# game_board.net
KiCad netlist of a schematic drawn in EAGLE
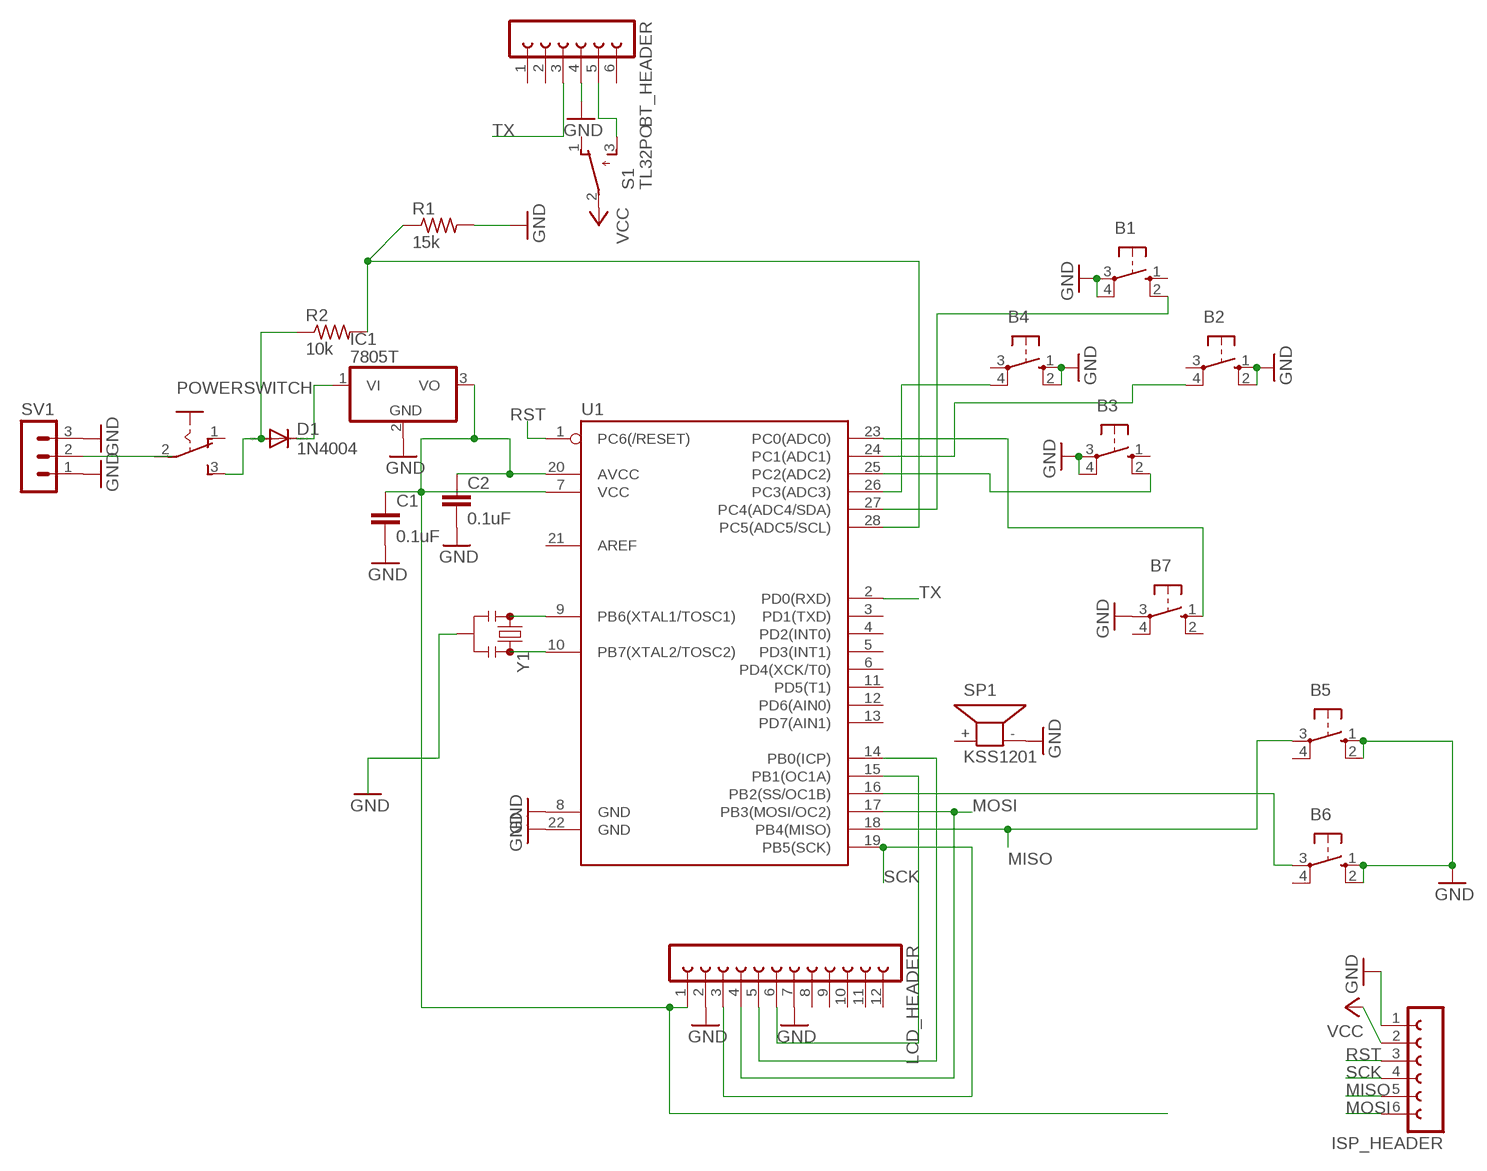
[diagram p0: schematic, sheet 1]

(export (version "E")
  (design (tool "Eeschema 10.0.6"))
  (components
    (comp (ref "B1")
      (value "10-XX")
      (footprint "eagle-import:B3F-10XX")
      (fields (field (name "MPN") "B3F-1000"))
      (libsource (lib "eagle-import") (part "10-XX"))
    )
    (comp (ref "B2")
      (value "10-XX")
      (footprint "eagle-import:B3F-10XX")
      (fields (field (name "MPN") "B3F-1000"))
      (libsource (lib "eagle-import") (part "10-XX"))
    )
    (comp (ref "B3")
      (value "10-XX")
      (footprint "eagle-import:B3F-10XX")
      (fields (field (name "MPN") "B3F-1000"))
      (libsource (lib "eagle-import") (part "10-XX"))
    )
    (comp (ref "B4")
      (value "10-XX")
      (footprint "eagle-import:B3F-10XX")
      (fields (field (name "MPN") "B3F-1000"))
      (libsource (lib "eagle-import") (part "10-XX"))
    )
    (comp (ref "B5")
      (value "10-XX")
      (footprint "eagle-import:B3F-10XX")
      (fields (field (name "MPN") "B3F-1000"))
      (libsource (lib "eagle-import") (part "10-XX"))
    )
    (comp (ref "B6")
      (value "10-XX")
      (footprint "eagle-import:B3F-10XX")
      (fields (field (name "MPN") "B3F-1000"))
      (libsource (lib "eagle-import") (part "10-XX"))
    )
    (comp (ref "B7")
      (value "10-XX")
      (footprint "eagle-import:B3F-10XX")
      (fields (field (name "MPN") "B3F-1000"))
      (libsource (lib "eagle-import") (part "10-XX"))
    )
    (comp (ref "BT_HEADER")
      (value "FE06W")
      (footprint "eagle-import:FE06W")
      (libsource (lib "eagle-import") (part "FE06W"))
    )
    (comp (ref "C1")
      (value "0.1uF")
      (footprint "eagle-import:0603-CAP")
      (libsource (lib "eagle-import") (part "0.1UF-25V(+80/-20%)(0603)"))
    )
    (comp (ref "C2")
      (value "0.1uF")
      (footprint "eagle-import:0603-CAP")
      (libsource (lib "eagle-import") (part "0.1UF-25V(+80/-20%)(0603)"))
    )
    (comp (ref "D1")
      (value "1N4004")
      (footprint "eagle-import:DO41-10")
      (libsource (lib "eagle-import") (part "1N4004"))
    )
    (comp (ref "IC1")
      (value "7805T")
      (footprint "eagle-import:TO220H")
      (libsource (lib "eagle-import") (part "78T05"))
    )
    (comp (ref "ISP_HEADER")
      (value "FE06W")
      (footprint "eagle-import:FE06W")
      (libsource (lib "eagle-import") (part "FE06W"))
    )
    (comp (ref "LCD_HEADER")
      (value "FE12W")
      (footprint "eagle-import:FE12W")
      (libsource (lib "eagle-import") (part "FE12W"))
    )
    (comp (ref "POWERSWITCH")
      (value "M251")
      (footprint "eagle-import:M251")
      (libsource (lib "eagle-import") (part "M251"))
    )
    (comp (ref "R1")
      (value "15k")
      (footprint "eagle-import:0204_7")
      (libsource (lib "eagle-import") (part "R-US_0204/7"))
    )
    (comp (ref "R2")
      (value "10k")
      (footprint "eagle-import:0204_7")
      (libsource (lib "eagle-import") (part "R-US_0204/7"))
    )
    (comp (ref "S1")
      (value "TL32PO")
      (footprint "eagle-import:TL3XPO")
      (libsource (lib "eagle-import") (part "TL32PO"))
    )
    (comp (ref "SP1")
      (value "KSS1201")
      (footprint "eagle-import:KSS1201")
      (libsource (lib "eagle-import") (part "KSS1201"))
    )
    (comp (ref "SV1")
      (value "MA03-1")
      (footprint "eagle-import:MA03-1")
      (libsource (lib "eagle-import") (part "MA03-1"))
    )
    (comp (ref "U1")
      (value "ATMEGA328P_PDIP")
      (footprint "eagle-import:DIL28-3")
      (libsource (lib "eagle-import") (part "ATMEGA328P_PDIP"))
    )
    (comp (ref "Y1")
      (value "RESONATORPTH")
      (footprint "eagle-import:RESONATOR-PTH")
      (libsource (lib "eagle-import") (part "RESONATORPTH"))
    )
  )
  (nets
    (net (code "1") (name "/MISO") (class "Default")
      (node (ref "B5") (pin "3") (pinfunction "P_3") (pintype "passive"))
      (node (ref "ISP_HEADER") (pin "5") (pinfunction "5_5") (pintype "passive"))
      (node (ref "U1") (pin "18") (pinfunction "PB4(MISO)_18") (pintype "bidirectional"))
    )
    (net (code "2") (name "/MOSI") (class "Default")
      (node (ref "ISP_HEADER") (pin "6") (pinfunction "6_6") (pintype "passive"))
      (node (ref "LCD_HEADER") (pin "4") (pinfunction "4_4") (pintype "passive"))
      (node (ref "U1") (pin "17") (pinfunction "PB3(MOSI/OC2)_17") (pintype "bidirectional"))
    )
    (net (code "3") (name "/RST") (class "Default")
      (node (ref "ISP_HEADER") (pin "3") (pinfunction "3_3") (pintype "passive"))
      (node (ref "U1") (pin "1") (pinfunction "PC6(/RESET)_1") (pintype "bidirectional"))
    )
    (net (code "4") (name "/SCK") (class "Default")
      (node (ref "ISP_HEADER") (pin "4") (pinfunction "4_4") (pintype "passive"))
      (node (ref "LCD_HEADER") (pin "3") (pinfunction "3_3") (pintype "passive"))
      (node (ref "U1") (pin "19") (pinfunction "PB5(SCK)_19") (pintype "bidirectional"))
    )
    (net (code "5") (name "/TX") (class "Default")
      (node (ref "BT_HEADER") (pin "3") (pinfunction "3_3") (pintype "passive"))
      (node (ref "U1") (pin "2") (pinfunction "PD0(RXD)_2") (pintype "bidirectional"))
    )
    (net (code "6") (name "GND") (class "Default")
      (node (ref "B1") (pin "3") (pinfunction "P_3") (pintype "passive"))
      (node (ref "B1") (pin "4") (pinfunction "P1_4") (pintype "passive"))
      (node (ref "B2") (pin "1") (pinfunction "S_1") (pintype "passive"))
      (node (ref "B2") (pin "2") (pinfunction "S1_2") (pintype "passive"))
      (node (ref "B3") (pin "3") (pinfunction "P_3") (pintype "passive"))
      (node (ref "B3") (pin "4") (pinfunction "P1_4") (pintype "passive"))
      (node (ref "B4") (pin "1") (pinfunction "S_1") (pintype "passive"))
      (node (ref "B4") (pin "2") (pinfunction "S1_2") (pintype "passive"))
      (node (ref "B5") (pin "1") (pinfunction "S_1") (pintype "passive"))
      (node (ref "B5") (pin "2") (pinfunction "S1_2") (pintype "passive"))
      (node (ref "B6") (pin "1") (pinfunction "S_1") (pintype "passive"))
      (node (ref "B6") (pin "2") (pinfunction "S1_2") (pintype "passive"))
      (node (ref "B7") (pin "3") (pinfunction "P_3") (pintype "passive"))
      (node (ref "BT_HEADER") (pin "4") (pinfunction "4_4") (pintype "passive"))
      (node (ref "C1") (pin "2") (pinfunction "2_2") (pintype "passive"))
      (node (ref "C2") (pin "2") (pinfunction "2_2") (pintype "passive"))
      (node (ref "IC1") (pin "2") (pinfunction "GND_2") (pintype "passive"))
      (node (ref "ISP_HEADER") (pin "1") (pinfunction "1_1") (pintype "passive"))
      (node (ref "LCD_HEADER") (pin "2") (pinfunction "2_2") (pintype "passive"))
      (node (ref "LCD_HEADER") (pin "7") (pinfunction "7_7") (pintype "passive"))
      (node (ref "R1") (pin "2") (pinfunction "2_2") (pintype "passive"))
      (node (ref "SP1") (pin "-") (pinfunction "2_-") (pintype "passive"))
      (node (ref "SV1") (pin "1") (pinfunction "1_1") (pintype "passive"))
      (node (ref "SV1") (pin "3") (pinfunction "3_3") (pintype "passive"))
      (node (ref "U1") (pin "22") (pinfunction "GND_22") (pintype "bidirectional"))
      (node (ref "U1") (pin "8") (pinfunction "GND_8") (pintype "bidirectional"))
      (node (ref "Y1") (pin "2") (pinfunction "2_2") (pintype "passive"))
    )
    (net (code "7") (name "Net-(B1-S1)") (class "Default")
      (node (ref "B1") (pin "2") (pinfunction "S1_2") (pintype "passive"))
      (node (ref "U1") (pin "27") (pinfunction "PC4(ADC4/SDA)_27") (pintype "bidirectional"))
    )
    (net (code "8") (name "Net-(B2-P1)") (class "Default")
      (node (ref "B2") (pin "4") (pinfunction "P1_4") (pintype "passive"))
      (node (ref "U1") (pin "24") (pinfunction "PC1(ADC1)_24") (pintype "bidirectional"))
    )
    (net (code "9") (name "Net-(B3-S1)") (class "Default")
      (node (ref "B3") (pin "2") (pinfunction "S1_2") (pintype "passive"))
      (node (ref "U1") (pin "25") (pinfunction "PC2(ADC2)_25") (pintype "bidirectional"))
    )
    (net (code "10") (name "Net-(B4-P1)") (class "Default")
      (node (ref "B4") (pin "4") (pinfunction "P1_4") (pintype "passive"))
      (node (ref "U1") (pin "26") (pinfunction "PC3(ADC3)_26") (pintype "bidirectional"))
    )
    (net (code "11") (name "Net-(B6-P)") (class "Default")
      (node (ref "B6") (pin "3") (pinfunction "P_3") (pintype "passive"))
      (node (ref "U1") (pin "16") (pinfunction "PB2(SS/OC1B)_16") (pintype "bidirectional"))
    )
    (net (code "12") (name "Net-(B7-S)") (class "Default")
      (node (ref "B7") (pin "1") (pinfunction "S_1") (pintype "passive"))
      (node (ref "U1") (pin "23") (pinfunction "PC0(ADC0)_23") (pintype "bidirectional"))
    )
    (net (code "13") (name "Net-(IC1-VI)") (class "Default")
      (node (ref "D1") (pin "C") (pinfunction "C_C") (pintype "passive"))
      (node (ref "IC1") (pin "1") (pinfunction "VI_1") (pintype "input"))
    )
    (net (code "14") (name "Net-(IC1-VO)") (class "Default")
      (node (ref "C1") (pin "1") (pinfunction "1_1") (pintype "passive"))
      (node (ref "C2") (pin "1") (pinfunction "1_1") (pintype "passive"))
      (node (ref "IC1") (pin "3") (pinfunction "VO_3") (pintype "passive"))
      (node (ref "LCD_HEADER") (pin "1") (pinfunction "1_1") (pintype "passive"))
      (node (ref "U1") (pin "20") (pinfunction "AVCC_20") (pintype "bidirectional"))
      (node (ref "U1") (pin "7") (pinfunction "VCC_7") (pintype "bidirectional"))
    )
    (net (code "15") (name "Net-(POWERSWITCH-P)") (class "Default")
      (node (ref "POWERSWITCH") (pin "2") (pinfunction "P_2") (pintype "passive"))
      (node (ref "SV1") (pin "2") (pinfunction "2_2") (pintype "passive"))
    )
    (net (code "16") (name "Net-(POWERSWITCH-S)") (class "Default")
      (node (ref "D1") (pin "A") (pinfunction "A_A") (pintype "passive"))
      (node (ref "POWERSWITCH") (pin "3") (pinfunction "S_3") (pintype "passive"))
      (node (ref "R2") (pin "1") (pinfunction "1_1") (pintype "passive"))
    )
    (net (code "17") (name "Net-(S1-S)") (class "Default")
      (node (ref "BT_HEADER") (pin "5") (pinfunction "5_5") (pintype "passive"))
      (node (ref "S1") (pin "3") (pinfunction "S_3") (pintype "passive"))
    )
    (net (code "18") (name "Net-(U1-PB0(ICP))") (class "Default")
      (node (ref "LCD_HEADER") (pin "5") (pinfunction "5_5") (pintype "passive"))
      (node (ref "U1") (pin "14") (pinfunction "PB0(ICP)_14") (pintype "bidirectional"))
    )
    (net (code "19") (name "Net-(U1-PB1(OC1A))") (class "Default")
      (node (ref "LCD_HEADER") (pin "6") (pinfunction "6_6") (pintype "passive"))
      (node (ref "U1") (pin "15") (pinfunction "PB1(OC1A)_15") (pintype "bidirectional"))
    )
    (net (code "20") (name "Net-(U1-PB6(XTAL1{slash}TOSC1))") (class "Default")
      (node (ref "U1") (pin "9") (pinfunction "PB6(XTAL1/TOSC1)_9") (pintype "bidirectional"))
      (node (ref "Y1") (pin "1") (pinfunction "1_1") (pintype "passive"))
    )
    (net (code "21") (name "Net-(U1-PB7(XTAL2{slash}TOSC2))") (class "Default")
      (node (ref "U1") (pin "10") (pinfunction "PB7(XTAL2/TOSC2)_10") (pintype "bidirectional"))
      (node (ref "Y1") (pin "3") (pinfunction "3_3") (pintype "passive"))
    )
    (net (code "22") (name "Net-(U1-PC5(ADC5{slash}SCL))") (class "Default")
      (node (ref "R1") (pin "1") (pinfunction "1_1") (pintype "passive"))
      (node (ref "R2") (pin "2") (pinfunction "2_2") (pintype "passive"))
      (node (ref "U1") (pin "28") (pinfunction "PC5(ADC5/SCL)_28") (pintype "bidirectional"))
    )
    (net (code "23") (name "VCC") (class "Default")
      (node (ref "ISP_HEADER") (pin "2") (pinfunction "2_2") (pintype "passive"))
      (node (ref "S1") (pin "2") (pinfunction "P_2") (pintype "passive"))
    )
    (net (code "24") (name "unconnected-(B1-S-Pad1)") (class "Default")
      (node (ref "B1") (pin "1") (pinfunction "S_1") (pintype "passive"))
    )
    (net (code "25") (name "unconnected-(B2-P-Pad3)") (class "Default")
      (node (ref "B2") (pin "3") (pinfunction "P_3") (pintype "passive"))
    )
    (net (code "26") (name "unconnected-(B3-S-Pad1)") (class "Default")
      (node (ref "B3") (pin "1") (pinfunction "S_1") (pintype "passive"))
    )
    (net (code "27") (name "unconnected-(B4-P-Pad3)") (class "Default")
      (node (ref "B4") (pin "3") (pinfunction "P_3") (pintype "passive"))
    )
    (net (code "28") (name "unconnected-(B5-P1-Pad4)") (class "Default")
      (node (ref "B5") (pin "4") (pinfunction "P1_4") (pintype "passive"))
    )
    (net (code "29") (name "unconnected-(B6-P1-Pad4)") (class "Default")
      (node (ref "B6") (pin "4") (pinfunction "P1_4") (pintype "passive"))
    )
    (net (code "30") (name "unconnected-(B7-P1-Pad4)") (class "Default")
      (node (ref "B7") (pin "4") (pinfunction "P1_4") (pintype "passive"))
    )
    (net (code "31") (name "unconnected-(B7-S1-Pad2)") (class "Default")
      (node (ref "B7") (pin "2") (pinfunction "S1_2") (pintype "passive"))
    )
    (net (code "32") (name "unconnected-(BT_HEADER-Pad1)") (class "Default")
      (node (ref "BT_HEADER") (pin "1") (pinfunction "1_1") (pintype "passive"))
    )
    (net (code "33") (name "unconnected-(BT_HEADER-Pad2)") (class "Default")
      (node (ref "BT_HEADER") (pin "2") (pinfunction "2_2") (pintype "passive"))
    )
    (net (code "34") (name "unconnected-(BT_HEADER-Pad6)") (class "Default")
      (node (ref "BT_HEADER") (pin "6") (pinfunction "6_6") (pintype "passive"))
    )
    (net (code "35") (name "unconnected-(LCD_HEADER-Pad8)") (class "Default")
      (node (ref "LCD_HEADER") (pin "8") (pinfunction "8_8") (pintype "passive"))
    )
    (net (code "36") (name "unconnected-(LCD_HEADER-Pad9)") (class "Default")
      (node (ref "LCD_HEADER") (pin "9") (pinfunction "9_9") (pintype "passive"))
    )
    (net (code "37") (name "unconnected-(LCD_HEADER-Pad10)") (class "Default")
      (node (ref "LCD_HEADER") (pin "10") (pinfunction "10_10") (pintype "passive"))
    )
    (net (code "38") (name "unconnected-(LCD_HEADER-Pad11)") (class "Default")
      (node (ref "LCD_HEADER") (pin "11") (pinfunction "11_11") (pintype "passive"))
    )
    (net (code "39") (name "unconnected-(LCD_HEADER-Pad12)") (class "Default")
      (node (ref "LCD_HEADER") (pin "12") (pinfunction "12_12") (pintype "passive"))
    )
    (net (code "40") (name "unconnected-(POWERSWITCH-O-Pad1)") (class "Default")
      (node (ref "POWERSWITCH") (pin "1") (pinfunction "O_1") (pintype "passive"))
    )
    (net (code "41") (name "unconnected-(S1-O-Pad1)") (class "Default")
      (node (ref "S1") (pin "1") (pinfunction "O_1") (pintype "passive"))
    )
    (net (code "42") (name "unconnected-(SP1-1-Pad+)") (class "Default")
      (node (ref "SP1") (pin "+") (pinfunction "1_+") (pintype "passive"))
    )
    (net (code "43") (name "unconnected-(U1-AREF-Pad21)") (class "Default")
      (node (ref "U1") (pin "21") (pinfunction "AREF_21") (pintype "bidirectional"))
    )
    (net (code "44") (name "unconnected-(U1-PD1(TXD)-Pad3)") (class "Default")
      (node (ref "U1") (pin "3") (pinfunction "PD1(TXD)_3") (pintype "bidirectional"))
    )
    (net (code "45") (name "unconnected-(U1-PD2(INT0)-Pad4)") (class "Default")
      (node (ref "U1") (pin "4") (pinfunction "PD2(INT0)_4") (pintype "bidirectional"))
    )
    (net (code "46") (name "unconnected-(U1-PD3(INT1)-Pad5)") (class "Default")
      (node (ref "U1") (pin "5") (pinfunction "PD3(INT1)_5") (pintype "bidirectional"))
    )
    (net (code "47") (name "unconnected-(U1-PD4(XCK{slash}T0)-Pad6)") (class "Default")
      (node (ref "U1") (pin "6") (pinfunction "PD4(XCK/T0)_6") (pintype "bidirectional"))
    )
    (net (code "48") (name "unconnected-(U1-PD5(T1)-Pad11)") (class "Default")
      (node (ref "U1") (pin "11") (pinfunction "PD5(T1)_11") (pintype "bidirectional"))
    )
    (net (code "49") (name "unconnected-(U1-PD6(AIN0)-Pad12)") (class "Default")
      (node (ref "U1") (pin "12") (pinfunction "PD6(AIN0)_12") (pintype "bidirectional"))
    )
    (net (code "50") (name "unconnected-(U1-PD7(AIN1)-Pad13)") (class "Default")
      (node (ref "U1") (pin "13") (pinfunction "PD7(AIN1)_13") (pintype "bidirectional"))
    )
  )
)
